# gatedriver_trafo_sma_compact_ACDC.net
KiCad netlist of a schematic drawn in EAGLE
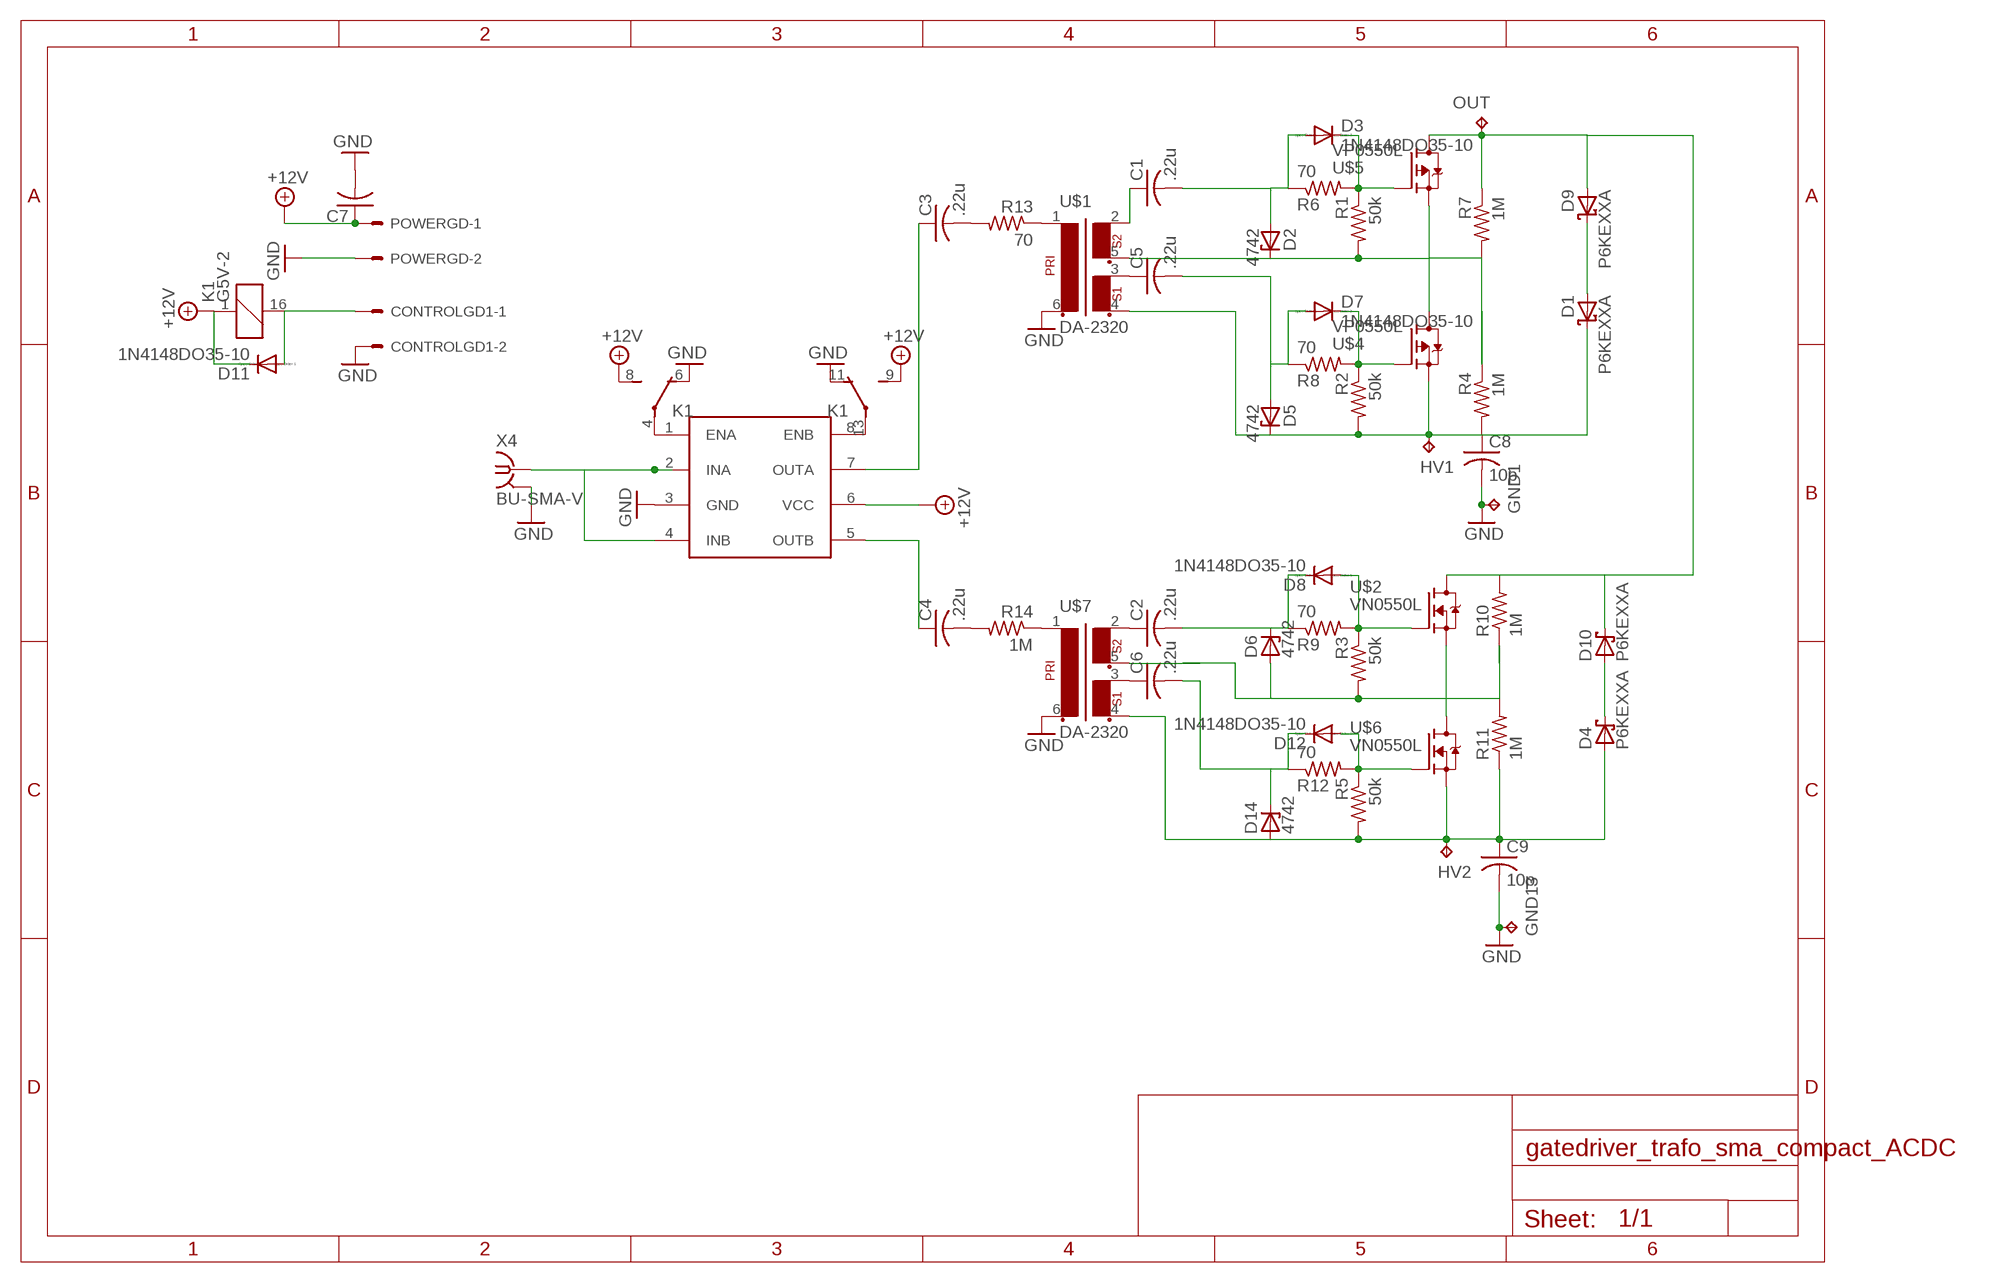
[diagram p0: schematic, sheet 1]

(export (version "E")
  (design (tool "Eeschema 10.0.6"))
  (components
    (comp (ref "C1")
      (value ".22u")
      (footprint "eagle-import:C050-055X075")
      (libsource (lib "eagle-import") (part "resistor_C-US050-055X075"))
    )
    (comp (ref "C2")
      (value ".22u")
      (footprint "eagle-import:C050-055X075")
      (libsource (lib "eagle-import") (part "resistor_C-US050-055X075"))
    )
    (comp (ref "C3")
      (value ".22u")
      (footprint "eagle-import:C050-055X075")
      (libsource (lib "eagle-import") (part "resistor_C-US050-055X075"))
    )
    (comp (ref "C4")
      (value ".22u")
      (footprint "eagle-import:C050-055X075")
      (libsource (lib "eagle-import") (part "resistor_C-US050-055X075"))
    )
    (comp (ref "C5")
      (value ".22u")
      (footprint "eagle-import:C050-055X075")
      (libsource (lib "eagle-import") (part "resistor_C-US050-055X075"))
    )
    (comp (ref "C6")
      (value ".22u")
      (footprint "eagle-import:C050-055X075")
      (libsource (lib "eagle-import") (part "resistor_C-US050-055X075"))
    )
    (comp (ref "C7")
      (value "C-US050-030X075")
      (footprint "eagle-import:C050-030X075")
      (libsource (lib "eagle-import") (part "C-US050-030X075"))
    )
    (comp (ref "C8")
      (value "10p")
      (footprint "eagle-import:C102-064X133")
      (libsource (lib "eagle-import") (part "resistor_C-US102-064X133"))
    )
    (comp (ref "C9")
      (value "10p")
      (footprint "eagle-import:C102-064X133")
      (libsource (lib "eagle-import") (part "resistor_C-US102-064X133"))
    )
    (comp (ref "CONTROLGD1")
      (value "KK-156-2")
      (footprint "eagle-import:KK-156-2")
      (libsource (lib "eagle-import") (part "KK-156-2"))
    )
    (comp (ref "D1")
      (value "P6KEXXA")
      (footprint "eagle-import:C1702-15")
      (libsource (lib "eagle-import") (part "P6KEXXA"))
    )
    (comp (ref "D2")
      (value "4742")
      (footprint "eagle-import:ZDIO-10")
      (libsource (lib "eagle-import") (part "ZENER-DIODEZD-10"))
    )
    (comp (ref "D3")
      (value "1N4148DO35-10")
      (footprint "eagle-import:DO35-10")
      (libsource (lib "eagle-import") (part "1N4148DO35-10"))
    )
    (comp (ref "D4")
      (value "P6KEXXA")
      (footprint "eagle-import:C1702-15")
      (libsource (lib "eagle-import") (part "P6KEXXA"))
    )
    (comp (ref "D5")
      (value "4742")
      (footprint "eagle-import:ZDIO-10")
      (libsource (lib "eagle-import") (part "ZENER-DIODEZD-10"))
    )
    (comp (ref "D6")
      (value "4742")
      (footprint "eagle-import:ZDIO-10")
      (libsource (lib "eagle-import") (part "ZENER-DIODEZD-10"))
    )
    (comp (ref "D7")
      (value "1N4148DO35-10")
      (footprint "eagle-import:DO35-10")
      (libsource (lib "eagle-import") (part "1N4148DO35-10"))
    )
    (comp (ref "D8")
      (value "1N4148DO35-10")
      (footprint "eagle-import:DO35-10")
      (libsource (lib "eagle-import") (part "1N4148DO35-10"))
    )
    (comp (ref "D9")
      (value "P6KEXXA")
      (footprint "eagle-import:C1702-15")
      (libsource (lib "eagle-import") (part "P6KEXXA"))
    )
    (comp (ref "D10")
      (value "P6KEXXA")
      (footprint "eagle-import:C1702-15")
      (libsource (lib "eagle-import") (part "P6KEXXA"))
    )
    (comp (ref "D11")
      (value "1N4148DO35-10")
      (footprint "eagle-import:DO35-10")
      (libsource (lib "eagle-import") (part "1N4148DO35-10"))
    )
    (comp (ref "D12")
      (value "1N4148DO35-10")
      (footprint "eagle-import:DO35-10")
      (libsource (lib "eagle-import") (part "1N4148DO35-10"))
    )
    (comp (ref "D14")
      (value "4742")
      (footprint "eagle-import:ZDIO-10")
      (libsource (lib "eagle-import") (part "ZENER-DIODEZD-10"))
    )
    (comp (ref "GND1")
      (value "TPPAD1-20Y")
      (footprint "eagle-import:P1-20Y")
      (libsource (lib "eagle-import") (part "TPPAD1-20Y"))
    )
    (comp (ref "GND13")
      (value "TPPAD1-20Y")
      (footprint "eagle-import:P1-20Y")
      (libsource (lib "eagle-import") (part "TPPAD1-20Y"))
    )
    (comp (ref "HV1")
      (value "TPPAD1-20Y")
      (footprint "eagle-import:P1-20Y")
      (libsource (lib "eagle-import") (part "TPPAD1-20Y"))
    )
    (comp (ref "HV2")
      (value "TPPAD1-20Y")
      (footprint "eagle-import:P1-20Y")
      (libsource (lib "eagle-import") (part "TPPAD1-20Y"))
    )
    (comp (ref "K1")
      (value "G5V-2")
      (footprint "eagle-import:G5V-2")
      (fields (field (name "MPN") "G5V-2 5DC"))
      (libsource (lib "eagle-import") (part "G5V-2"))
    )
    (comp (ref "OUT")
      (value "TPPAD1-20Y")
      (footprint "eagle-import:P1-20Y")
      (libsource (lib "eagle-import") (part "TPPAD1-20Y"))
    )
    (comp (ref "POWERGD")
      (value "KK-156-2")
      (footprint "eagle-import:KK-156-2")
      (libsource (lib "eagle-import") (part "KK-156-2"))
    )
    (comp (ref "R1")
      (value "50k")
      (footprint "eagle-import:0207_10")
      (libsource (lib "eagle-import") (part "R-US_0207/10"))
    )
    (comp (ref "R2")
      (value "50k")
      (footprint "eagle-import:0207_10")
      (libsource (lib "eagle-import") (part "R-US_0207/10"))
    )
    (comp (ref "R3")
      (value "50k")
      (footprint "eagle-import:0207_10")
      (libsource (lib "eagle-import") (part "R-US_0207/10"))
    )
    (comp (ref "R4")
      (value "1M")
      (footprint "eagle-import:0207_10")
      (libsource (lib "eagle-import") (part "R-US_0207/10"))
    )
    (comp (ref "R5")
      (value "50k")
      (footprint "eagle-import:0207_10")
      (libsource (lib "eagle-import") (part "R-US_0207/10"))
    )
    (comp (ref "R6")
      (value "70")
      (footprint "eagle-import:0207_10")
      (libsource (lib "eagle-import") (part "R-US_0207/10"))
    )
    (comp (ref "R7")
      (value "1M")
      (footprint "eagle-import:0207_10")
      (libsource (lib "eagle-import") (part "R-US_0207/10"))
    )
    (comp (ref "R8")
      (value "70")
      (footprint "eagle-import:0207_10")
      (libsource (lib "eagle-import") (part "R-US_0207/10"))
    )
    (comp (ref "R9")
      (value "70")
      (footprint "eagle-import:0207_10")
      (libsource (lib "eagle-import") (part "R-US_0207/10"))
    )
    (comp (ref "R10")
      (value "1M")
      (footprint "eagle-import:0207_10")
      (libsource (lib "eagle-import") (part "R-US_0207/10"))
    )
    (comp (ref "R11")
      (value "1M")
      (footprint "eagle-import:0207_10")
      (libsource (lib "eagle-import") (part "R-US_0207/10"))
    )
    (comp (ref "R12")
      (value "70")
      (footprint "eagle-import:0207_10")
      (libsource (lib "eagle-import") (part "R-US_0207/10"))
    )
    (comp (ref "R13")
      (value "70")
      (footprint "eagle-import:0207_10")
      (libsource (lib "eagle-import") (part "R-US_0207/10"))
    )
    (comp (ref "R14")
      (value "1M")
      (footprint "eagle-import:0207_10")
      (libsource (lib "eagle-import") (part "R-US_0207/10"))
    )
    (comp (ref "U$1")
      (value "DA-2320")
      (footprint "eagle-import:DIL06")
      (libsource (lib "eagle-import") (part "DA-2320"))
    )
    (comp (ref "U$2")
      (value "VN0550L")
      (footprint "eagle-import:TO92L")
      (libsource (lib "eagle-import") (part "VN0550L"))
    )
    (comp (ref "U$3")
      (value "UCC27425")
      (footprint "eagle-import:DIL08")
      (libsource (lib "eagle-import") (part "UCC27425"))
    )
    (comp (ref "U$4")
      (value "VP0550L")
      (footprint "eagle-import:TO92L")
      (libsource (lib "eagle-import") (part "VP0550L"))
    )
    (comp (ref "U$5")
      (value "VP0550L")
      (footprint "eagle-import:TO92L")
      (libsource (lib "eagle-import") (part "VP0550L"))
    )
    (comp (ref "U$6")
      (value "VN0550L")
      (footprint "eagle-import:TO92L")
      (libsource (lib "eagle-import") (part "VN0550L"))
    )
    (comp (ref "U$7")
      (value "DA-2320")
      (footprint "eagle-import:DIL06")
      (libsource (lib "eagle-import") (part "DA-2320"))
    )
    (comp (ref "X4")
      (value "BU-SMA-V")
      (footprint "eagle-import:BU-SMA-V")
      (libsource (lib "eagle-import") (part "BU-SMA-V"))
    )
  )
  (nets
    (net (code "1") (name "+12V") (class "Default")
      (node (ref "C7") (pin "1") (pinfunction "1_1") (pintype "passive"))
      (node (ref "D11") (pin "C") (pinfunction "C_C") (pintype "passive"))
      (node (ref "K1") (pin "1") (pinfunction "1_1") (pintype "passive"))
      (node (ref "K1") (pin "8") (pinfunction "S_8") (pintype "passive"))
      (node (ref "K1") (pin "9") (pinfunction "S_9") (pintype "passive"))
      (node (ref "POWERGD") (pin "1") (pinfunction "S_1") (pintype "passive"))
      (node (ref "U$3") (pin "6") (pinfunction "VCC_6") (pintype "bidirectional"))
    )
    (net (code "2") (name "GND") (class "Default")
      (node (ref "C7") (pin "2") (pinfunction "2_2") (pintype "passive"))
      (node (ref "C8") (pin "2") (pinfunction "2_2") (pintype "passive"))
      (node (ref "C9") (pin "2") (pinfunction "2_2") (pintype "passive"))
      (node (ref "CONTROLGD1") (pin "2") (pinfunction "S_2") (pintype "passive"))
      (node (ref "GND1") (pin "TP") (pinfunction "TP_TP") (pintype "input"))
      (node (ref "GND13") (pin "TP") (pinfunction "TP_TP") (pintype "input"))
      (node (ref "K1") (pin "11") (pinfunction "O_11") (pintype "passive"))
      (node (ref "K1") (pin "6") (pinfunction "O_6") (pintype "passive"))
      (node (ref "POWERGD") (pin "2") (pinfunction "S_2") (pintype "passive"))
      (node (ref "U$1") (pin "6") (pinfunction "2_6") (pintype "passive"))
      (node (ref "U$3") (pin "3") (pinfunction "GND_3") (pintype "bidirectional"))
      (node (ref "U$7") (pin "6") (pinfunction "2_6") (pintype "passive"))
      (node (ref "X4") (pin "2") (pinfunction "2_2") (pintype "passive"))
      (node (ref "X4") (pin "3") (pinfunction "2_3") (pintype "passive"))
      (node (ref "X4") (pin "4") (pinfunction "2_4") (pintype "passive"))
      (node (ref "X4") (pin "5") (pinfunction "2_5") (pintype "passive"))
    )
    (net (code "3") (name "Net-(C1-Pad2)") (class "Default")
      (node (ref "C1") (pin "2") (pinfunction "2_2") (pintype "passive"))
      (node (ref "D2") (pin "A") (pinfunction "A_A") (pintype "passive"))
      (node (ref "D3") (pin "A") (pinfunction "A_A") (pintype "passive"))
      (node (ref "R6") (pin "1") (pinfunction "1_1") (pintype "passive"))
    )
    (net (code "4") (name "Net-(C2-Pad2)") (class "Default")
      (node (ref "C2") (pin "2") (pinfunction "2_2") (pintype "passive"))
      (node (ref "D6") (pin "C") (pinfunction "C_C") (pintype "passive"))
      (node (ref "D8") (pin "C") (pinfunction "C_C") (pintype "passive"))
      (node (ref "R9") (pin "1") (pinfunction "1_1") (pintype "passive"))
    )
    (net (code "5") (name "Net-(C3-Pad2)") (class "Default")
      (node (ref "C3") (pin "2") (pinfunction "2_2") (pintype "passive"))
      (node (ref "R13") (pin "2") (pinfunction "2_2") (pintype "passive"))
    )
    (net (code "6") (name "Net-(C4-Pad2)") (class "Default")
      (node (ref "C4") (pin "2") (pinfunction "2_2") (pintype "passive"))
      (node (ref "R14") (pin "2") (pinfunction "2_2") (pintype "passive"))
    )
    (net (code "7") (name "Net-(C5-Pad2)") (class "Default")
      (node (ref "C5") (pin "2") (pinfunction "2_2") (pintype "passive"))
      (node (ref "D5") (pin "A") (pinfunction "A_A") (pintype "passive"))
      (node (ref "D7") (pin "A") (pinfunction "A_A") (pintype "passive"))
      (node (ref "R8") (pin "1") (pinfunction "1_1") (pintype "passive"))
    )
    (net (code "8") (name "Net-(C6-Pad2)") (class "Default")
      (node (ref "C6") (pin "2") (pinfunction "2_2") (pintype "passive"))
      (node (ref "D12") (pin "C") (pinfunction "C_C") (pintype "passive"))
      (node (ref "D14") (pin "C") (pinfunction "C_C") (pintype "passive"))
      (node (ref "R12") (pin "1") (pinfunction "1_1") (pintype "passive"))
    )
    (net (code "9") (name "Net-(CONTROLGD1A-S)") (class "Default")
      (node (ref "CONTROLGD1") (pin "1") (pinfunction "S_1") (pintype "passive"))
      (node (ref "D11") (pin "A") (pinfunction "A_A") (pintype "passive"))
      (node (ref "K1") (pin "16") (pinfunction "2_16") (pintype "passive"))
    )
    (net (code "10") (name "Net-(D1-PadA)") (class "Default")
      (node (ref "D1") (pin "A") (pinfunction "A_A") (pintype "passive"))
      (node (ref "D9") (pin "C") (pinfunction "C_C") (pintype "passive"))
    )
    (net (code "11") (name "Net-(D10-PadA)") (class "Default")
      (node (ref "D10") (pin "A") (pinfunction "A_A") (pintype "passive"))
      (node (ref "D4") (pin "C") (pinfunction "C_C") (pintype "passive"))
    )
    (net (code "12") (name "Net-(K1A-P)") (class "Default")
      (node (ref "K1") (pin "4") (pinfunction "P_4") (pintype "passive"))
      (node (ref "U$3") (pin "1") (pinfunction "ENA_1") (pintype "bidirectional"))
    )
    (net (code "13") (name "Net-(K1B-P)") (class "Default")
      (node (ref "K1") (pin "13") (pinfunction "P_13") (pintype "passive"))
      (node (ref "U$3") (pin "8") (pinfunction "ENB_8") (pintype "bidirectional"))
    )
    (net (code "14") (name "Net-(R13-Pad1)") (class "Default")
      (node (ref "R13") (pin "1") (pinfunction "1_1") (pintype "passive"))
      (node (ref "U$1") (pin "1") (pinfunction "1_1") (pintype "passive"))
    )
    (net (code "15") (name "Net-(R14-Pad1)") (class "Default")
      (node (ref "R14") (pin "1") (pinfunction "1_1") (pintype "passive"))
      (node (ref "U$7") (pin "1") (pinfunction "1_1") (pintype "passive"))
    )
    (net (code "16") (name "Net-(U$1-3)") (class "Default")
      (node (ref "C8") (pin "1") (pinfunction "1_1") (pintype "passive"))
      (node (ref "D1") (pin "C") (pinfunction "C_C") (pintype "passive"))
      (node (ref "D5") (pin "C") (pinfunction "C_C") (pintype "passive"))
      (node (ref "HV1") (pin "TP") (pinfunction "TP_TP") (pintype "input"))
      (node (ref "R2") (pin "2") (pinfunction "2_2") (pintype "passive"))
      (node (ref "R4") (pin "2") (pinfunction "2_2") (pintype "passive"))
      (node (ref "U$1") (pin "4") (pinfunction "3_4") (pintype "passive"))
      (node (ref "U$4") (pin "3") (pinfunction "S_3") (pintype "passive"))
    )
    (net (code "17") (name "Net-(U$1-4)") (class "Default")
      (node (ref "C5") (pin "1") (pinfunction "1_1") (pintype "passive"))
      (node (ref "U$1") (pin "3") (pinfunction "4_3") (pintype "passive"))
    )
    (net (code "18") (name "Net-(U$1-6)") (class "Default")
      (node (ref "C1") (pin "1") (pinfunction "1_1") (pintype "passive"))
      (node (ref "U$1") (pin "2") (pinfunction "6_2") (pintype "passive"))
    )
    (net (code "19") (name "Net-(U$2-D)") (class "Default")
      (node (ref "D10") (pin "C") (pinfunction "C_C") (pintype "passive"))
      (node (ref "D9") (pin "A") (pinfunction "A_A") (pintype "passive"))
      (node (ref "OUT") (pin "TP") (pinfunction "TP_TP") (pintype "input"))
      (node (ref "R10") (pin "2") (pinfunction "2_2") (pintype "passive"))
      (node (ref "R7") (pin "1") (pinfunction "1_1") (pintype "passive"))
      (node (ref "U$2") (pin "1") (pinfunction "D_1") (pintype "passive"))
      (node (ref "U$5") (pin "1") (pinfunction "D_1") (pintype "passive"))
    )
    (net (code "20") (name "Net-(U$2-G)") (class "Default")
      (node (ref "D8") (pin "A") (pinfunction "A_A") (pintype "passive"))
      (node (ref "R3") (pin "1") (pinfunction "1_1") (pintype "passive"))
      (node (ref "R9") (pin "2") (pinfunction "2_2") (pintype "passive"))
      (node (ref "U$2") (pin "2") (pinfunction "G_2") (pintype "passive"))
    )
    (net (code "21") (name "Net-(U$2-S)") (class "Default")
      (node (ref "D6") (pin "A") (pinfunction "A_A") (pintype "passive"))
      (node (ref "R10") (pin "1") (pinfunction "1_1") (pintype "passive"))
      (node (ref "R11") (pin "2") (pinfunction "2_2") (pintype "passive"))
      (node (ref "R3") (pin "2") (pinfunction "2_2") (pintype "passive"))
      (node (ref "U$2") (pin "3") (pinfunction "S_3") (pintype "passive"))
      (node (ref "U$6") (pin "1") (pinfunction "D_1") (pintype "passive"))
    )
    (net (code "22") (name "Net-(U$3-INA)") (class "Default")
      (node (ref "U$3") (pin "2") (pinfunction "INA_2") (pintype "bidirectional"))
      (node (ref "U$3") (pin "4") (pinfunction "INB_4") (pintype "bidirectional"))
      (node (ref "X4") (pin "1") (pinfunction "1_1") (pintype "passive"))
    )
    (net (code "23") (name "Net-(U$3-OUTA)") (class "Default")
      (node (ref "C3") (pin "1") (pinfunction "1_1") (pintype "passive"))
      (node (ref "U$3") (pin "7") (pinfunction "OUTA_7") (pintype "bidirectional"))
    )
    (net (code "24") (name "Net-(U$3-OUTB)") (class "Default")
      (node (ref "C4") (pin "1") (pinfunction "1_1") (pintype "passive"))
      (node (ref "U$3") (pin "5") (pinfunction "OUTB_5") (pintype "bidirectional"))
    )
    (net (code "25") (name "Net-(U$4-D)") (class "Default")
      (node (ref "D2") (pin "C") (pinfunction "C_C") (pintype "passive"))
      (node (ref "R1") (pin "2") (pinfunction "2_2") (pintype "passive"))
      (node (ref "R4") (pin "1") (pinfunction "1_1") (pintype "passive"))
      (node (ref "R7") (pin "2") (pinfunction "2_2") (pintype "passive"))
      (node (ref "U$1") (pin "5") (pinfunction "5_5") (pintype "passive"))
      (node (ref "U$4") (pin "1") (pinfunction "D_1") (pintype "passive"))
      (node (ref "U$5") (pin "3") (pinfunction "S_3") (pintype "passive"))
    )
    (net (code "26") (name "Net-(U$4-G)") (class "Default")
      (node (ref "D7") (pin "C") (pinfunction "C_C") (pintype "passive"))
      (node (ref "R2") (pin "1") (pinfunction "1_1") (pintype "passive"))
      (node (ref "R8") (pin "2") (pinfunction "2_2") (pintype "passive"))
      (node (ref "U$4") (pin "2") (pinfunction "G_2") (pintype "passive"))
    )
    (net (code "27") (name "Net-(U$5-G)") (class "Default")
      (node (ref "D3") (pin "C") (pinfunction "C_C") (pintype "passive"))
      (node (ref "R1") (pin "1") (pinfunction "1_1") (pintype "passive"))
      (node (ref "R6") (pin "2") (pinfunction "2_2") (pintype "passive"))
      (node (ref "U$5") (pin "2") (pinfunction "G_2") (pintype "passive"))
    )
    (net (code "28") (name "Net-(U$6-G)") (class "Default")
      (node (ref "D12") (pin "A") (pinfunction "A_A") (pintype "passive"))
      (node (ref "R12") (pin "2") (pinfunction "2_2") (pintype "passive"))
      (node (ref "R5") (pin "1") (pinfunction "1_1") (pintype "passive"))
      (node (ref "U$6") (pin "2") (pinfunction "G_2") (pintype "passive"))
    )
    (net (code "29") (name "Net-(U$6-S)") (class "Default")
      (node (ref "C9") (pin "1") (pinfunction "1_1") (pintype "passive"))
      (node (ref "D14") (pin "A") (pinfunction "A_A") (pintype "passive"))
      (node (ref "D4") (pin "A") (pinfunction "A_A") (pintype "passive"))
      (node (ref "HV2") (pin "TP") (pinfunction "TP_TP") (pintype "input"))
      (node (ref "R11") (pin "1") (pinfunction "1_1") (pintype "passive"))
      (node (ref "R5") (pin "2") (pinfunction "2_2") (pintype "passive"))
      (node (ref "U$6") (pin "3") (pinfunction "S_3") (pintype "passive"))
      (node (ref "U$7") (pin "4") (pinfunction "3_4") (pintype "passive"))
    )
    (net (code "30") (name "Net-(U$7-4)") (class "Default")
      (node (ref "C6") (pin "1") (pinfunction "1_1") (pintype "passive"))
      (node (ref "U$7") (pin "3") (pinfunction "4_3") (pintype "passive"))
    )
    (net (code "31") (name "Net-(U$7-6)") (class "Default")
      (node (ref "C2") (pin "1") (pinfunction "1_1") (pintype "passive"))
      (node (ref "U$7") (pin "2") (pinfunction "6_2") (pintype "passive"))
    )
    (net (code "32") (name "unconnected-(U$7-Pad5)") (class "Default")
      (node (ref "U$7") (pin "5") (pinfunction "5_5") (pintype "passive"))
    )
  )
)
